# Communications.net
KiCad netlist of a schematic drawn in Altium Designer
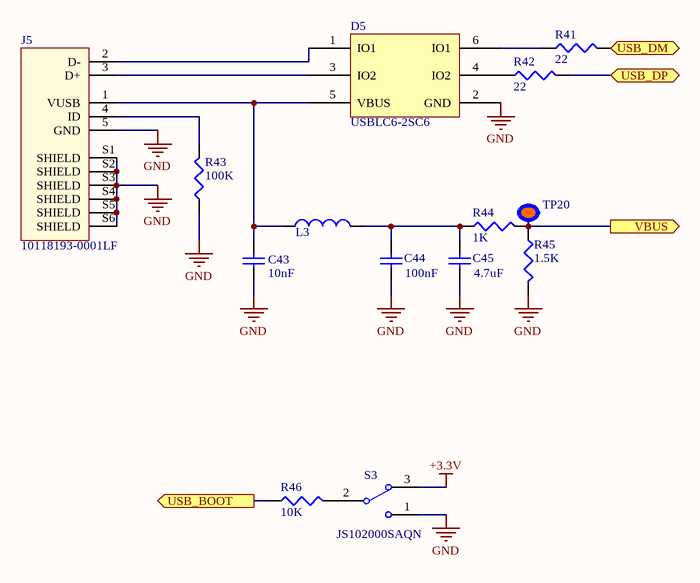
[diagram p0: Communications.SchDoc]

(export (version "E")
  (design (tool "Eeschema 10.0.6"))
  (components
    (comp (ref "C43")
      (value "10nF")
      (footprint "RES_0603")
      (description "Capacitor")
      (fields
        (field (name "MANUFACTURER") "Samsung Electro-Mechanics")
        (field (name "MANUFACTURER PART NUMBER") "CL10B103KB8NCNC")
      )
      (libsource (lib "Miscellaneous Devices") (part "Cap"))
    )
    (comp (ref "C44")
      (value "100nF")
      (footprint "RES_0603")
      (description "Capacitor")
      (fields
        (field (name "MANUFACTURER") "AVX Corporation")
        (field (name "MANUFACTURER PART NUMBER") "06035G104ZAT2A")
      )
      (libsource (lib "Miscellaneous Devices") (part "Cap"))
    )
    (comp (ref "C45")
      (value "4.7uF")
      (footprint "RES_0805")
      (description "Capacitor")
      (fields
        (field (name "MANUFACTURER") "Samsung Electro-Mechanics")
        (field (name "MANUFACTURER PART NUMBER") "CL21A475KACLRNC")
      )
      (libsource (lib "Miscellaneous Devices") (part "Cap"))
    )
    (comp (ref "D5")
      (value "USBLC6-2SC6")
      (footprint "SOT23-6L")
      (description "TVS DIODE 5.25V 17V SOT23-6")
      (fields (field (name "MANUFACTURER") "STMicroelectronics"))
      (libsource (lib "Custom") (part "USBLC6-2SC6"))
    )
    (comp (ref "J5")
      (value "10118193-0001LF")
      (footprint "10118193-0001LF")
      (description "Single Port 5 Contact Shielded SMT MICRO USB B-Type Receptacle")
      (fields (field (name "MANUFACTURER") "Amphenol ICC"))
      (libsource (lib "Custom") (part "10118193-0001LF"))
    )
    (comp (ref "L3")
      (value "BLM18PG221SZ1D")
      (footprint "RES_0603")
      (description "Inductor")
      (fields (field (name "MANUFACTURER") "Murata Electronics"))
      (libsource (lib "Miscellaneous Devices") (part "Inductor"))
    )
    (comp (ref "R41")
      (value "22")
      (footprint "RES_0603")
      (description "CRGCQ0603J22R")
      (fields (field (name "MANUFACTURER") "TE Connectivity Passive Product"))
      (libsource (lib "Miscellaneous Devices") (part "Res3"))
    )
    (comp (ref "R42")
      (value "22")
      (footprint "RES_0603")
      (description "CRGCQ0603J22R")
      (fields (field (name "MANUFACTURER") "TE Connectivity Passive Product"))
      (libsource (lib "Miscellaneous Devices") (part "Res3"))
    )
    (comp (ref "R43")
      (value "100K")
      (footprint "RES_0603")
      (description "Resistor")
      (fields
        (field (name "MANUFACTURER") "Susumu")
        (field (name "MANUFACTURER PART NUMBER") "RR0816P-104-D")
      )
      (libsource (lib "Miscellaneous Devices") (part "Res3"))
    )
    (comp (ref "R44")
      (value "1K")
      (footprint "RES_0603")
      (description "Resistor")
      (fields
        (field (name "MANUFACTURER") "Susumu")
        (field (name "MANUFACTURER PART NUMBER") "RR0816P-102-D")
      )
      (libsource (lib "Miscellaneous Devices") (part "Res3"))
    )
    (comp (ref "R45")
      (value "1.5K")
      (footprint "RES_0603")
      (description "Resistor")
      (fields
        (field (name "MANUFACTURER") "TE Connectivity Passive Product")
        (field (name "MANUFACTURER PART NUMBER") "A121524CT-ND")
      )
      (libsource (lib "Miscellaneous Devices") (part "Res3"))
    )
    (comp (ref "R46")
      (value "10K")
      (footprint "RES_0805")
      (description "Resistor")
      (fields
        (field (name "MANUFACTURER") "Susumu")
        (field (name "MANUFACTURER PART NUMBER") "RR1220P-103-D")
      )
      (libsource (lib "Miscellaneous Devices") (part "Res3"))
    )
    (comp (ref "S3")
      (value "JS102000SAQN")
      (footprint "JS102011SAQN")
      (description "SWITCH SLIDE SPDT 1MA 5V")
      (fields (field (name "MANUFACTURER") "C&K") (field (name "MANUFACTURER PART NUMBER") "JS102011SAQN"))
      (libsource (lib "Miscellaneous Devices") (part "SW-SPDT"))
    )
    (comp (ref "TP20")
      (value "loop test point")
      (footprint "Test Point Mt Hole")
      (description "Test Point Loop Miniature Keysone")
      (fields
        (field (name "MANUFACTURER") "Keystone Electronics")
        (field (name "MANUFACTURER PART NUMBER") "5003")
      )
      (libsource (lib "Custom") (part "Test Point"))
    )
  )
  (nets
    (net (code "1") (name "+3.3V") (class "Default")
      (node (ref "S3") (pin "3") (pinfunction "3_3") (pintype "passive"))
    )
    (net (code "2") (name "/USB_BOOT") (class "Default")
      (node (ref "R46") (pin "1") (pinfunction "1_1") (pintype "passive"))
    )
    (net (code "3") (name "/USB_DM") (class "Default")
      (node (ref "R41") (pin "2") (pinfunction "2_2") (pintype "passive"))
    )
    (net (code "4") (name "/USB_DP") (class "Default")
      (node (ref "R42") (pin "2") (pinfunction "2_2") (pintype "passive"))
    )
    (net (code "5") (name "/VBUS") (class "Default")
      (node (ref "R44") (pin "2") (pinfunction "2_2") (pintype "passive"))
      (node (ref "R45") (pin "1") (pinfunction "1_1") (pintype "passive"))
      (node (ref "TP20") (pin "1") (pinfunction "1_1") (pintype "passive"))
    )
    (net (code "6") (name "GND") (class "Default")
      (node (ref "C43") (pin "1") (pinfunction "1_1") (pintype "passive"))
      (node (ref "C44") (pin "1") (pinfunction "1_1") (pintype "passive"))
      (node (ref "C45") (pin "1") (pinfunction "1_1") (pintype "passive"))
      (node (ref "D5") (pin "2") (pinfunction "GND_2") (pintype "passive"))
      (node (ref "J5") (pin "5") (pinfunction "GND_5") (pintype "passive"))
      (node (ref "J5") (pin "S1") (pinfunction "SHIELD_S1") (pintype "passive"))
      (node (ref "J5") (pin "S2") (pinfunction "SHIELD_S2") (pintype "passive"))
      (node (ref "J5") (pin "S3") (pinfunction "SHIELD_S3") (pintype "passive"))
      (node (ref "J5") (pin "S4") (pinfunction "SHIELD_S4") (pintype "passive"))
      (node (ref "J5") (pin "S5") (pinfunction "SHIELD_S5") (pintype "passive"))
      (node (ref "J5") (pin "S6") (pinfunction "SHIELD_S6") (pintype "passive"))
      (node (ref "R43") (pin "1") (pinfunction "1_1") (pintype "passive"))
      (node (ref "R45") (pin "2") (pinfunction "2_2") (pintype "passive"))
      (node (ref "S3") (pin "1") (pinfunction "1_1") (pintype "passive"))
    )
    (net (code "7") (name "Net-(C44-Pad2)") (class "Default")
      (node (ref "C44") (pin "2") (pinfunction "2_2") (pintype "passive"))
      (node (ref "C45") (pin "2") (pinfunction "2_2") (pintype "passive"))
      (node (ref "L3") (pin "2") (pinfunction "2_2") (pintype "passive"))
      (node (ref "R44") (pin "1") (pinfunction "1_1") (pintype "passive"))
    )
    (net (code "8") (name "Net-(D5-IO1-Pad6)") (class "Default")
      (node (ref "D5") (pin "6") (pinfunction "IO1_6") (pintype "passive"))
      (node (ref "R41") (pin "1") (pinfunction "1_1") (pintype "passive"))
    )
    (net (code "9") (name "Net-(D5-IO2-Pad4)") (class "Default")
      (node (ref "D5") (pin "4") (pinfunction "IO2_4") (pintype "passive"))
      (node (ref "R42") (pin "1") (pinfunction "1_1") (pintype "passive"))
    )
    (net (code "10") (name "Net-(D5-VBUS)") (class "Default")
      (node (ref "C43") (pin "2") (pinfunction "2_2") (pintype "passive"))
      (node (ref "D5") (pin "5") (pinfunction "VBUS_5") (pintype "passive"))
      (node (ref "J5") (pin "1") (pinfunction "VUSB_1") (pintype "passive"))
      (node (ref "L3") (pin "1") (pinfunction "1_1") (pintype "passive"))
    )
    (net (code "11") (name "Net-(J5-D+)") (class "Default")
      (node (ref "D5") (pin "3") (pinfunction "IO2_3") (pintype "passive"))
      (node (ref "J5") (pin "3") (pinfunction "D+_3") (pintype "passive"))
    )
    (net (code "12") (name "Net-(J5-D-)") (class "Default")
      (node (ref "D5") (pin "1") (pinfunction "IO1_1") (pintype "passive"))
      (node (ref "J5") (pin "2") (pinfunction "D-_2") (pintype "passive"))
    )
    (net (code "13") (name "Net-(J5-ID)") (class "Default")
      (node (ref "J5") (pin "4") (pinfunction "ID_4") (pintype "passive"))
      (node (ref "R43") (pin "2") (pinfunction "2_2") (pintype "passive"))
    )
    (net (code "14") (name "Net-(R46-Pad2)") (class "Default")
      (node (ref "R46") (pin "2") (pinfunction "2_2") (pintype "passive"))
      (node (ref "S3") (pin "2") (pinfunction "2_2") (pintype "passive"))
    )
  )
)
